# USB2514_REGULATOR.net
KiCad netlist of a schematic drawn in Altium Designer
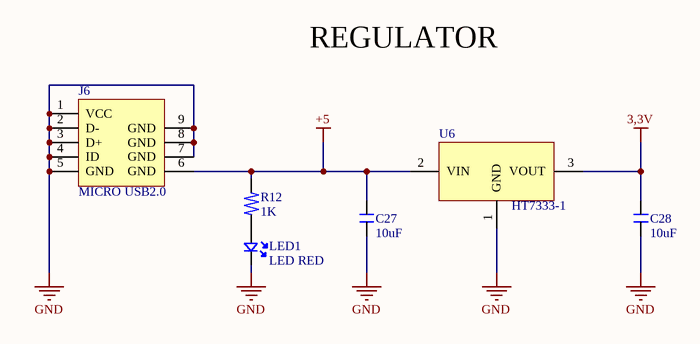
[diagram p0: USB2514 REGULATOR.SchDoc]

(export (version "E")
  (design (tool "Eeschema 10.0.6"))
  (components
    (comp (ref "C27")
      (value "10uF")
      (footprint "CAPC3216X10N-1206")
      (libsource (lib "SCH_LIB") (part "CAP_1206_22uF"))
    )
    (comp (ref "C28")
      (value "10uF")
      (footprint "CAPC3216X10N-1206")
      (libsource (lib "SCH_LIB") (part "CAP_1206_22uF"))
    )
    (comp (ref "J6")
      (value "MICRO USB2.0")
      (footprint "USB_CON_10118192-0001LF_SMD")
      (description "USB - micro B USB 2.0 Receptacle Connector 5 Position Surface Mount, Right Angle")
      (fields
        (field (name "MANUFACTURER") "Amphenol ICC (FCI)")
        (field (name "MANUFACTURING PART NUMBER") "10118192-0002LF")
      )
      (libsource (lib "SCH_LIB") (part "USB_CON-10118192-0002LF-SMD"))
    )
    (comp (ref "LED1")
      (value "LED RED")
      (footprint "LED_0603")
      (libsource (lib "SCH_LIB") (part "LED_RED_0603"))
    )
    (comp (ref "R12")
      (value "1K")
      (footprint "RESC1608X06N-0603")
      (libsource (lib "SCH_LIB") (part "RES_0603_1K"))
    )
    (comp (ref "U6")
      (value "HT7333-1")
      (footprint "SOT89-150P350X150-3N")
      (description "HT7333-1\r\n30V, 250mA TinyPowerTM LDO")
      (libsource (lib "SCH_LIB") (part "HT7333-1"))
    )
  )
  (nets
    (net (code "1") (name "+5") (class "Default")
      (node (ref "C27") (pin "2") (pinfunction "2_2") (pintype "passive"))
      (node (ref "J6") (pin "6") (pinfunction "GND_6") (pintype "passive"))
      (node (ref "R12") (pin "2") (pinfunction "2_2") (pintype "passive"))
      (node (ref "U6") (pin "2") (pinfunction "VIN_2") (pintype "passive"))
    )
    (net (code "2") (name "3,3V") (class "Default")
      (node (ref "C28") (pin "2") (pinfunction "2_2") (pintype "passive"))
      (node (ref "U6") (pin "3") (pinfunction "VOUT_3") (pintype "passive"))
    )
    (net (code "3") (name "GND") (class "Default")
      (node (ref "C27") (pin "1") (pinfunction "1_1") (pintype "passive"))
      (node (ref "C28") (pin "1") (pinfunction "1_1") (pintype "passive"))
      (node (ref "J6") (pin "1") (pinfunction "VCC_1") (pintype "passive"))
      (node (ref "J6") (pin "2") (pinfunction "D-_2") (pintype "passive"))
      (node (ref "J6") (pin "3") (pinfunction "D+_3") (pintype "passive"))
      (node (ref "J6") (pin "4") (pinfunction "ID_4") (pintype "passive"))
      (node (ref "J6") (pin "5") (pinfunction "GND_5") (pintype "passive"))
      (node (ref "J6") (pin "7") (pinfunction "GND_7") (pintype "passive"))
      (node (ref "J6") (pin "8") (pinfunction "GND_8") (pintype "passive"))
      (node (ref "J6") (pin "9") (pinfunction "GND_9") (pintype "passive"))
      (node (ref "LED1") (pin "C") (pinfunction "C_C") (pintype "passive"))
      (node (ref "U6") (pin "1") (pinfunction "GND_1") (pintype "passive"))
    )
    (net (code "4") (name "Net-(LED1-PadA)") (class "Default")
      (node (ref "LED1") (pin "A") (pinfunction "A_A") (pintype "passive"))
      (node (ref "R12") (pin "1") (pinfunction "1_1") (pintype "passive"))
    )
  )
)
